# MegaWithL298.net
KiCad netlist of a schematic drawn in EAGLE
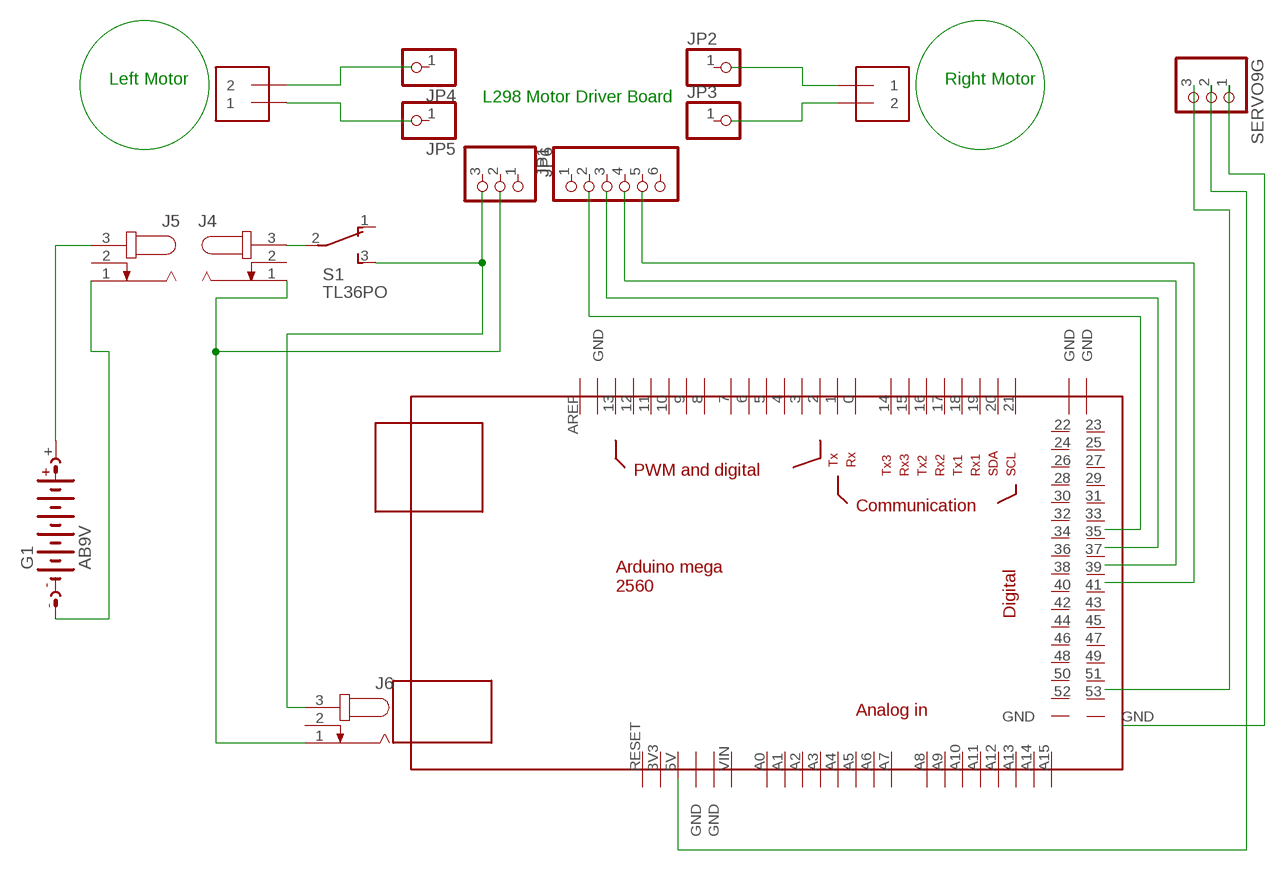
[diagram p0: schematic, sheet 1]

(export (version "E")
  (design (tool "Eeschema 10.0.6"))
  (components
    (comp (ref "G1")
      (value "AB9V")
      (footprint "eagle-import:AB9V")
      (libsource (lib "eagle-import") (part "AB9V"))
    )
    (comp (ref "J2")
      (value "1X2-3.5MM")
      (footprint "eagle-import:1X2-3.5MM")
      (libsource (lib "eagle-import") (part "1X2-3.5MM"))
    )
    (comp (ref "J3")
      (value "1X2-3.5MM")
      (footprint "eagle-import:1X2-3.5MM")
      (libsource (lib "eagle-import") (part "1X2-3.5MM"))
    )
    (comp (ref "J4")
      (value "RAPC7120")
      (footprint "eagle-import:RAPC712")
      (libsource (lib "eagle-import") (part "RAPC7120"))
    )
    (comp (ref "J5")
      (value "RAPC7120")
      (footprint "eagle-import:RAPC712")
      (libsource (lib "eagle-import") (part "RAPC7120"))
    )
    (comp (ref "J6")
      (value "RAPC7120")
      (footprint "eagle-import:RAPC712")
      (libsource (lib "eagle-import") (part "RAPC7120"))
    )
    (comp (ref "JP1")
      (value "PINHD-1X6")
      (footprint "eagle-import:1X06")
      (libsource (lib "eagle-import") (part "PINHD-1X6"))
    )
    (comp (ref "JP2")
      (value "PINHD-1X1")
      (footprint "eagle-import:1X01")
      (libsource (lib "eagle-import") (part "PINHD-1X1"))
    )
    (comp (ref "JP3")
      (value "PINHD-1X1")
      (footprint "eagle-import:1X01")
      (libsource (lib "eagle-import") (part "PINHD-1X1"))
    )
    (comp (ref "JP4")
      (value "PINHD-1X1")
      (footprint "eagle-import:1X01")
      (libsource (lib "eagle-import") (part "PINHD-1X1"))
    )
    (comp (ref "JP5")
      (value "PINHD-1X1")
      (footprint "eagle-import:1X01")
      (libsource (lib "eagle-import") (part "PINHD-1X1"))
    )
    (comp (ref "JP6")
      (value "PINHD-1X3")
      (footprint "eagle-import:1X03")
      (libsource (lib "eagle-import") (part "PINHD-1X3"))
    )
    (comp (ref "S1")
      (value "TL36PO")
      (footprint "eagle-import:TL3XPO")
      (libsource (lib "eagle-import") (part "TL36PO"))
    )
    (comp (ref "SERVO9G")
      (value "PINHD-1X3")
      (footprint "eagle-import:1X03")
      (libsource (lib "eagle-import") (part "PINHD-1X3"))
    )
    (comp (ref "U$1")
      (value "MEGA_DEVICE")
      (footprint "eagle-import:MEGABOX")
      (libsource (lib "eagle-import") (part "MEGA_DEVICE"))
    )
  )
  (nets
    (net (code "1") (name "Net-(G1-Pad+)") (class "Default")
      (node (ref "G1") (pin "+") (pinfunction "+_+") (pintype "passive"))
      (node (ref "J5") (pin "3") (pinfunction "3_3") (pintype "passive"))
    )
    (net (code "2") (name "Net-(G1-Pad-)") (class "Default")
      (node (ref "G1") (pin "-") (pinfunction "-_-") (pintype "passive"))
      (node (ref "J5") (pin "1") (pinfunction "1_1") (pintype "passive"))
    )
    (net (code "3") (name "Net-(J4-Pad1)") (class "Default")
      (node (ref "J4") (pin "1") (pinfunction "1_1") (pintype "passive"))
      (node (ref "J6") (pin "1") (pinfunction "1_1") (pintype "passive"))
    )
    (net (code "4") (name "Net-(S1-P)") (class "Default")
      (node (ref "J4") (pin "3") (pinfunction "3_3") (pintype "passive"))
      (node (ref "S1") (pin "2") (pinfunction "P_2") (pintype "passive"))
    )
    (net (code "5") (name "Net-(S1-S)") (class "Default")
      (node (ref "J6") (pin "3") (pinfunction "3_3") (pintype "passive"))
      (node (ref "S1") (pin "3") (pinfunction "S_3") (pintype "passive"))
    )
    (net (code "6") (name "unconnected-(J2-Pad1)") (class "Default")
      (node (ref "J2") (pin "1") (pinfunction "1_1") (pintype "passive"))
    )
    (net (code "7") (name "unconnected-(J2-Pad2)") (class "Default")
      (node (ref "J2") (pin "2") (pinfunction "2_2") (pintype "passive"))
    )
    (net (code "8") (name "unconnected-(J3-Pad1)") (class "Default")
      (node (ref "J3") (pin "1") (pinfunction "1_1") (pintype "passive"))
    )
    (net (code "9") (name "unconnected-(J3-Pad2)") (class "Default")
      (node (ref "J3") (pin "2") (pinfunction "2_2") (pintype "passive"))
    )
    (net (code "10") (name "unconnected-(J4-Pad2)") (class "Default")
      (node (ref "J4") (pin "2") (pinfunction "2_2") (pintype "passive"))
    )
    (net (code "11") (name "unconnected-(J5-Pad2)") (class "Default")
      (node (ref "J5") (pin "2") (pinfunction "2_2") (pintype "passive"))
    )
    (net (code "12") (name "unconnected-(J6-Pad2)") (class "Default")
      (node (ref "J6") (pin "2") (pinfunction "2_2") (pintype "passive"))
    )
    (net (code "13") (name "unconnected-(JP1-Pad1)") (class "Default")
      (node (ref "JP1") (pin "1") (pinfunction "1_1") (pintype "passive"))
    )
    (net (code "14") (name "unconnected-(JP1-Pad2)") (class "Default")
      (node (ref "JP1") (pin "2") (pinfunction "2_2") (pintype "passive"))
    )
    (net (code "15") (name "unconnected-(JP1-Pad3)") (class "Default")
      (node (ref "JP1") (pin "3") (pinfunction "3_3") (pintype "passive"))
    )
    (net (code "16") (name "unconnected-(JP1-Pad4)") (class "Default")
      (node (ref "JP1") (pin "4") (pinfunction "4_4") (pintype "passive"))
    )
    (net (code "17") (name "unconnected-(JP1-Pad5)") (class "Default")
      (node (ref "JP1") (pin "5") (pinfunction "5_5") (pintype "passive"))
    )
    (net (code "18") (name "unconnected-(JP1-Pad6)") (class "Default")
      (node (ref "JP1") (pin "6") (pinfunction "6_6") (pintype "passive"))
    )
    (net (code "19") (name "unconnected-(JP2-Pad1)") (class "Default")
      (node (ref "JP2") (pin "1") (pinfunction "1_1") (pintype "passive"))
    )
    (net (code "20") (name "unconnected-(JP3-Pad1)") (class "Default")
      (node (ref "JP3") (pin "1") (pinfunction "1_1") (pintype "passive"))
    )
    (net (code "21") (name "unconnected-(JP4-Pad1)") (class "Default")
      (node (ref "JP4") (pin "1") (pinfunction "1_1") (pintype "passive"))
    )
    (net (code "22") (name "unconnected-(JP5-Pad1)") (class "Default")
      (node (ref "JP5") (pin "1") (pinfunction "1_1") (pintype "passive"))
    )
    (net (code "23") (name "unconnected-(JP6-Pad1)") (class "Default")
      (node (ref "JP6") (pin "1") (pinfunction "1_1") (pintype "passive"))
    )
    (net (code "24") (name "unconnected-(JP6-Pad2)") (class "Default")
      (node (ref "JP6") (pin "2") (pinfunction "2_2") (pintype "passive"))
    )
    (net (code "25") (name "unconnected-(JP6-Pad3)") (class "Default")
      (node (ref "JP6") (pin "3") (pinfunction "3_3") (pintype "passive"))
    )
    (net (code "26") (name "unconnected-(S1-O-Pad1)") (class "Default")
      (node (ref "S1") (pin "1") (pinfunction "O_1") (pintype "passive"))
    )
    (net (code "27") (name "unconnected-(SERVO9G-Pad1)") (class "Default")
      (node (ref "SERVO9G") (pin "1") (pinfunction "1_1") (pintype "passive"))
    )
    (net (code "28") (name "unconnected-(SERVO9G-Pad2)") (class "Default")
      (node (ref "SERVO9G") (pin "2") (pinfunction "2_2") (pintype "passive"))
    )
    (net (code "29") (name "unconnected-(SERVO9G-Pad3)") (class "Default")
      (node (ref "SERVO9G") (pin "3") (pinfunction "3_3") (pintype "passive"))
    )
    (net (code "30") (name "unconnected-(U$1-GND-PadGND@1)") (class "Default")
      (node (ref "U$1") (pin "GND@1") (pinfunction "GND_GND@1") (pintype "bidirectional"))
    )
    (net (code "31") (name "unconnected-(U$1-GND-PadGND@2)") (class "Default")
      (node (ref "U$1") (pin "GND@2") (pinfunction "GND_GND@2") (pintype "bidirectional"))
    )
    (net (code "32") (name "unconnected-(U$1-GND-PadGND@3)") (class "Default")
      (node (ref "U$1") (pin "GND@3") (pinfunction "GND_GND@3") (pintype "bidirectional"))
    )
    (net (code "33") (name "unconnected-(U$1-GND-PadGND@4)") (class "Default")
      (node (ref "U$1") (pin "GND@4") (pinfunction "GND_GND@4") (pintype "bidirectional"))
    )
    (net (code "34") (name "unconnected-(U$1-GND-PadGND@5)") (class "Default")
      (node (ref "U$1") (pin "GND@5") (pinfunction "GND_GND@5") (pintype "bidirectional"))
    )
    (net (code "35") (name "unconnected-(U$1-GND-PadGND@6)") (class "Default")
      (node (ref "U$1") (pin "GND@6") (pinfunction "GND_GND@6") (pintype "bidirectional"))
    )
    (net (code "36") (name "unconnected-(U$1-GND-PadGND@7)") (class "Default")
      (node (ref "U$1") (pin "GND@7") (pinfunction "GND_GND@7") (pintype "bidirectional"))
    )
    (net (code "37") (name "unconnected-(U$1-Pad0)") (class "Default")
      (node (ref "U$1") (pin "0") (pinfunction "0_0") (pintype "bidirectional"))
    )
    (net (code "38") (name "unconnected-(U$1-Pad1)") (class "Default")
      (node (ref "U$1") (pin "1") (pinfunction "1_1") (pintype "bidirectional"))
    )
    (net (code "39") (name "unconnected-(U$1-Pad2)") (class "Default")
      (node (ref "U$1") (pin "2") (pinfunction "2_2") (pintype "bidirectional"))
    )
    (net (code "40") (name "unconnected-(U$1-Pad3)") (class "Default")
      (node (ref "U$1") (pin "3") (pinfunction "3_3") (pintype "bidirectional"))
    )
    (net (code "41") (name "unconnected-(U$1-Pad3V3)") (class "Default")
      (node (ref "U$1") (pin "3V3") (pinfunction "3V3_3V3") (pintype "bidirectional"))
    )
    (net (code "42") (name "unconnected-(U$1-Pad4)") (class "Default")
      (node (ref "U$1") (pin "4") (pinfunction "4_4") (pintype "bidirectional"))
    )
    (net (code "43") (name "unconnected-(U$1-Pad5)") (class "Default")
      (node (ref "U$1") (pin "5") (pinfunction "5_5") (pintype "bidirectional"))
    )
    (net (code "44") (name "unconnected-(U$1-Pad5V)") (class "Default")
      (node (ref "U$1") (pin "5V") (pinfunction "5V_5V") (pintype "bidirectional"))
    )
    (net (code "45") (name "unconnected-(U$1-Pad6)") (class "Default")
      (node (ref "U$1") (pin "6") (pinfunction "6_6") (pintype "bidirectional"))
    )
    (net (code "46") (name "unconnected-(U$1-Pad7)") (class "Default")
      (node (ref "U$1") (pin "7") (pinfunction "7_7") (pintype "bidirectional"))
    )
    (net (code "47") (name "unconnected-(U$1-Pad8)") (class "Default")
      (node (ref "U$1") (pin "8") (pinfunction "8_8") (pintype "bidirectional"))
    )
    (net (code "48") (name "unconnected-(U$1-Pad9)") (class "Default")
      (node (ref "U$1") (pin "9") (pinfunction "9_9") (pintype "bidirectional"))
    )
    (net (code "49") (name "unconnected-(U$1-Pad10)") (class "Default")
      (node (ref "U$1") (pin "10") (pinfunction "10_10") (pintype "bidirectional"))
    )
    (net (code "50") (name "unconnected-(U$1-Pad11)") (class "Default")
      (node (ref "U$1") (pin "11") (pinfunction "11_11") (pintype "bidirectional"))
    )
    (net (code "51") (name "unconnected-(U$1-Pad12)") (class "Default")
      (node (ref "U$1") (pin "12") (pinfunction "12_12") (pintype "bidirectional"))
    )
    (net (code "52") (name "unconnected-(U$1-Pad13)") (class "Default")
      (node (ref "U$1") (pin "13") (pinfunction "13_13") (pintype "bidirectional"))
    )
    (net (code "53") (name "unconnected-(U$1-Pad14)") (class "Default")
      (node (ref "U$1") (pin "14") (pinfunction "14_14") (pintype "bidirectional"))
    )
    (net (code "54") (name "unconnected-(U$1-Pad15)") (class "Default")
      (node (ref "U$1") (pin "15") (pinfunction "15_15") (pintype "bidirectional"))
    )
    (net (code "55") (name "unconnected-(U$1-Pad16)") (class "Default")
      (node (ref "U$1") (pin "16") (pinfunction "16_16") (pintype "bidirectional"))
    )
    (net (code "56") (name "unconnected-(U$1-Pad17)") (class "Default")
      (node (ref "U$1") (pin "17") (pinfunction "17_17") (pintype "bidirectional"))
    )
    (net (code "57") (name "unconnected-(U$1-Pad18)") (class "Default")
      (node (ref "U$1") (pin "18") (pinfunction "18_18") (pintype "bidirectional"))
    )
    (net (code "58") (name "unconnected-(U$1-Pad19)") (class "Default")
      (node (ref "U$1") (pin "19") (pinfunction "19_19") (pintype "bidirectional"))
    )
    (net (code "59") (name "unconnected-(U$1-Pad20)") (class "Default")
      (node (ref "U$1") (pin "20") (pinfunction "20_20") (pintype "bidirectional"))
    )
    (net (code "60") (name "unconnected-(U$1-Pad21)") (class "Default")
      (node (ref "U$1") (pin "21") (pinfunction "21_21") (pintype "bidirectional"))
    )
    (net (code "61") (name "unconnected-(U$1-Pad22)") (class "Default")
      (node (ref "U$1") (pin "22") (pinfunction "22_22") (pintype "bidirectional"))
    )
    (net (code "62") (name "unconnected-(U$1-Pad23)") (class "Default")
      (node (ref "U$1") (pin "23") (pinfunction "23_23") (pintype "bidirectional"))
    )
    (net (code "63") (name "unconnected-(U$1-Pad24)") (class "Default")
      (node (ref "U$1") (pin "24") (pinfunction "24_24") (pintype "bidirectional"))
    )
    (net (code "64") (name "unconnected-(U$1-Pad25)") (class "Default")
      (node (ref "U$1") (pin "25") (pinfunction "25_25") (pintype "bidirectional"))
    )
    (net (code "65") (name "unconnected-(U$1-Pad26)") (class "Default")
      (node (ref "U$1") (pin "26") (pinfunction "26_26") (pintype "bidirectional"))
    )
    (net (code "66") (name "unconnected-(U$1-Pad27)") (class "Default")
      (node (ref "U$1") (pin "27") (pinfunction "27_27") (pintype "bidirectional"))
    )
    (net (code "67") (name "unconnected-(U$1-Pad28)") (class "Default")
      (node (ref "U$1") (pin "28") (pinfunction "28_28") (pintype "bidirectional"))
    )
    (net (code "68") (name "unconnected-(U$1-Pad29)") (class "Default")
      (node (ref "U$1") (pin "29") (pinfunction "29_29") (pintype "bidirectional"))
    )
    (net (code "69") (name "unconnected-(U$1-Pad30)") (class "Default")
      (node (ref "U$1") (pin "30") (pinfunction "30_30") (pintype "bidirectional"))
    )
    (net (code "70") (name "unconnected-(U$1-Pad31)") (class "Default")
      (node (ref "U$1") (pin "31") (pinfunction "31_31") (pintype "bidirectional"))
    )
    (net (code "71") (name "unconnected-(U$1-Pad32)") (class "Default")
      (node (ref "U$1") (pin "32") (pinfunction "32_32") (pintype "bidirectional"))
    )
    (net (code "72") (name "unconnected-(U$1-Pad33)") (class "Default")
      (node (ref "U$1") (pin "33") (pinfunction "33_33") (pintype "bidirectional"))
    )
    (net (code "73") (name "unconnected-(U$1-Pad34)") (class "Default")
      (node (ref "U$1") (pin "34") (pinfunction "34_34") (pintype "bidirectional"))
    )
    (net (code "74") (name "unconnected-(U$1-Pad35)") (class "Default")
      (node (ref "U$1") (pin "35") (pinfunction "35_35") (pintype "bidirectional"))
    )
    (net (code "75") (name "unconnected-(U$1-Pad36)") (class "Default")
      (node (ref "U$1") (pin "36") (pinfunction "36_36") (pintype "bidirectional"))
    )
    (net (code "76") (name "unconnected-(U$1-Pad37)") (class "Default")
      (node (ref "U$1") (pin "37") (pinfunction "37_37") (pintype "bidirectional"))
    )
    (net (code "77") (name "unconnected-(U$1-Pad38)") (class "Default")
      (node (ref "U$1") (pin "38") (pinfunction "38_38") (pintype "bidirectional"))
    )
    (net (code "78") (name "unconnected-(U$1-Pad39)") (class "Default")
      (node (ref "U$1") (pin "39") (pinfunction "39_39") (pintype "bidirectional"))
    )
    (net (code "79") (name "unconnected-(U$1-Pad40)") (class "Default")
      (node (ref "U$1") (pin "40") (pinfunction "40_40") (pintype "bidirectional"))
    )
    (net (code "80") (name "unconnected-(U$1-Pad41)") (class "Default")
      (node (ref "U$1") (pin "41") (pinfunction "41_41") (pintype "bidirectional"))
    )
    (net (code "81") (name "unconnected-(U$1-Pad42)") (class "Default")
      (node (ref "U$1") (pin "42") (pinfunction "42_42") (pintype "bidirectional"))
    )
    (net (code "82") (name "unconnected-(U$1-Pad43)") (class "Default")
      (node (ref "U$1") (pin "43") (pinfunction "43_43") (pintype "bidirectional"))
    )
    (net (code "83") (name "unconnected-(U$1-Pad44)") (class "Default")
      (node (ref "U$1") (pin "44") (pinfunction "44_44") (pintype "bidirectional"))
    )
    (net (code "84") (name "unconnected-(U$1-Pad45)") (class "Default")
      (node (ref "U$1") (pin "45") (pinfunction "45_45") (pintype "bidirectional"))
    )
    (net (code "85") (name "unconnected-(U$1-Pad46)") (class "Default")
      (node (ref "U$1") (pin "46") (pinfunction "46_46") (pintype "bidirectional"))
    )
    (net (code "86") (name "unconnected-(U$1-Pad47)") (class "Default")
      (node (ref "U$1") (pin "47") (pinfunction "47_47") (pintype "bidirectional"))
    )
    (net (code "87") (name "unconnected-(U$1-Pad48)") (class "Default")
      (node (ref "U$1") (pin "48") (pinfunction "48_48") (pintype "bidirectional"))
    )
    (net (code "88") (name "unconnected-(U$1-Pad49)") (class "Default")
      (node (ref "U$1") (pin "49") (pinfunction "49_49") (pintype "bidirectional"))
    )
    (net (code "89") (name "unconnected-(U$1-Pad50)") (class "Default")
      (node (ref "U$1") (pin "50") (pinfunction "50_50") (pintype "bidirectional"))
    )
    (net (code "90") (name "unconnected-(U$1-Pad51)") (class "Default")
      (node (ref "U$1") (pin "51") (pinfunction "51_51") (pintype "bidirectional"))
    )
    (net (code "91") (name "unconnected-(U$1-Pad52)") (class "Default")
      (node (ref "U$1") (pin "52") (pinfunction "52_52") (pintype "bidirectional"))
    )
    (net (code "92") (name "unconnected-(U$1-Pad53)") (class "Default")
      (node (ref "U$1") (pin "53") (pinfunction "53_53") (pintype "bidirectional"))
    )
    (net (code "93") (name "unconnected-(U$1-PadA0)") (class "Default")
      (node (ref "U$1") (pin "A0") (pinfunction "A0_A0") (pintype "bidirectional"))
    )
    (net (code "94") (name "unconnected-(U$1-PadA1)") (class "Default")
      (node (ref "U$1") (pin "A1") (pinfunction "A1_A1") (pintype "bidirectional"))
    )
    (net (code "95") (name "unconnected-(U$1-PadA2)") (class "Default")
      (node (ref "U$1") (pin "A2") (pinfunction "A2_A2") (pintype "bidirectional"))
    )
    (net (code "96") (name "unconnected-(U$1-PadA3)") (class "Default")
      (node (ref "U$1") (pin "A3") (pinfunction "A3_A3") (pintype "bidirectional"))
    )
    (net (code "97") (name "unconnected-(U$1-PadA4)") (class "Default")
      (node (ref "U$1") (pin "A4") (pinfunction "A4_A4") (pintype "bidirectional"))
    )
    (net (code "98") (name "unconnected-(U$1-PadA5)") (class "Default")
      (node (ref "U$1") (pin "A5") (pinfunction "A5_A5") (pintype "bidirectional"))
    )
    (net (code "99") (name "unconnected-(U$1-PadA6)") (class "Default")
      (node (ref "U$1") (pin "A6") (pinfunction "A6_A6") (pintype "bidirectional"))
    )
    (net (code "100") (name "unconnected-(U$1-PadA7)") (class "Default")
      (node (ref "U$1") (pin "A7") (pinfunction "A7_A7") (pintype "bidirectional"))
    )
    (net (code "101") (name "unconnected-(U$1-PadA8)") (class "Default")
      (node (ref "U$1") (pin "A8") (pinfunction "A8_A8") (pintype "bidirectional"))
    )
    (net (code "102") (name "unconnected-(U$1-PadA9)") (class "Default")
      (node (ref "U$1") (pin "A9") (pinfunction "A9_A9") (pintype "bidirectional"))
    )
    (net (code "103") (name "unconnected-(U$1-PadA10)") (class "Default")
      (node (ref "U$1") (pin "A10") (pinfunction "A10_A10") (pintype "bidirectional"))
    )
    (net (code "104") (name "unconnected-(U$1-PadA11)") (class "Default")
      (node (ref "U$1") (pin "A11") (pinfunction "A11_A11") (pintype "bidirectional"))
    )
    (net (code "105") (name "unconnected-(U$1-PadA12)") (class "Default")
      (node (ref "U$1") (pin "A12") (pinfunction "A12_A12") (pintype "bidirectional"))
    )
    (net (code "106") (name "unconnected-(U$1-PadA13)") (class "Default")
      (node (ref "U$1") (pin "A13") (pinfunction "A13_A13") (pintype "bidirectional"))
    )
    (net (code "107") (name "unconnected-(U$1-PadA14)") (class "Default")
      (node (ref "U$1") (pin "A14") (pinfunction "A14_A14") (pintype "bidirectional"))
    )
    (net (code "108") (name "unconnected-(U$1-PadA15)") (class "Default")
      (node (ref "U$1") (pin "A15") (pinfunction "A15_A15") (pintype "bidirectional"))
    )
    (net (code "109") (name "unconnected-(U$1-PadAREF)") (class "Default")
      (node (ref "U$1") (pin "AREF") (pinfunction "AREF_AREF") (pintype "bidirectional"))
    )
    (net (code "110") (name "unconnected-(U$1-PadRESET)") (class "Default")
      (node (ref "U$1") (pin "RESET") (pinfunction "RESET_RESET") (pintype "bidirectional"))
    )
    (net (code "111") (name "unconnected-(U$1-PadVIN)") (class "Default")
      (node (ref "U$1") (pin "VIN") (pinfunction "VIN_VIN") (pintype "bidirectional"))
    )
  )
)
